# SH2_-_24V_BUCK-BOOST_CONVERTER.net
KiCad netlist of a schematic drawn in Altium Designer
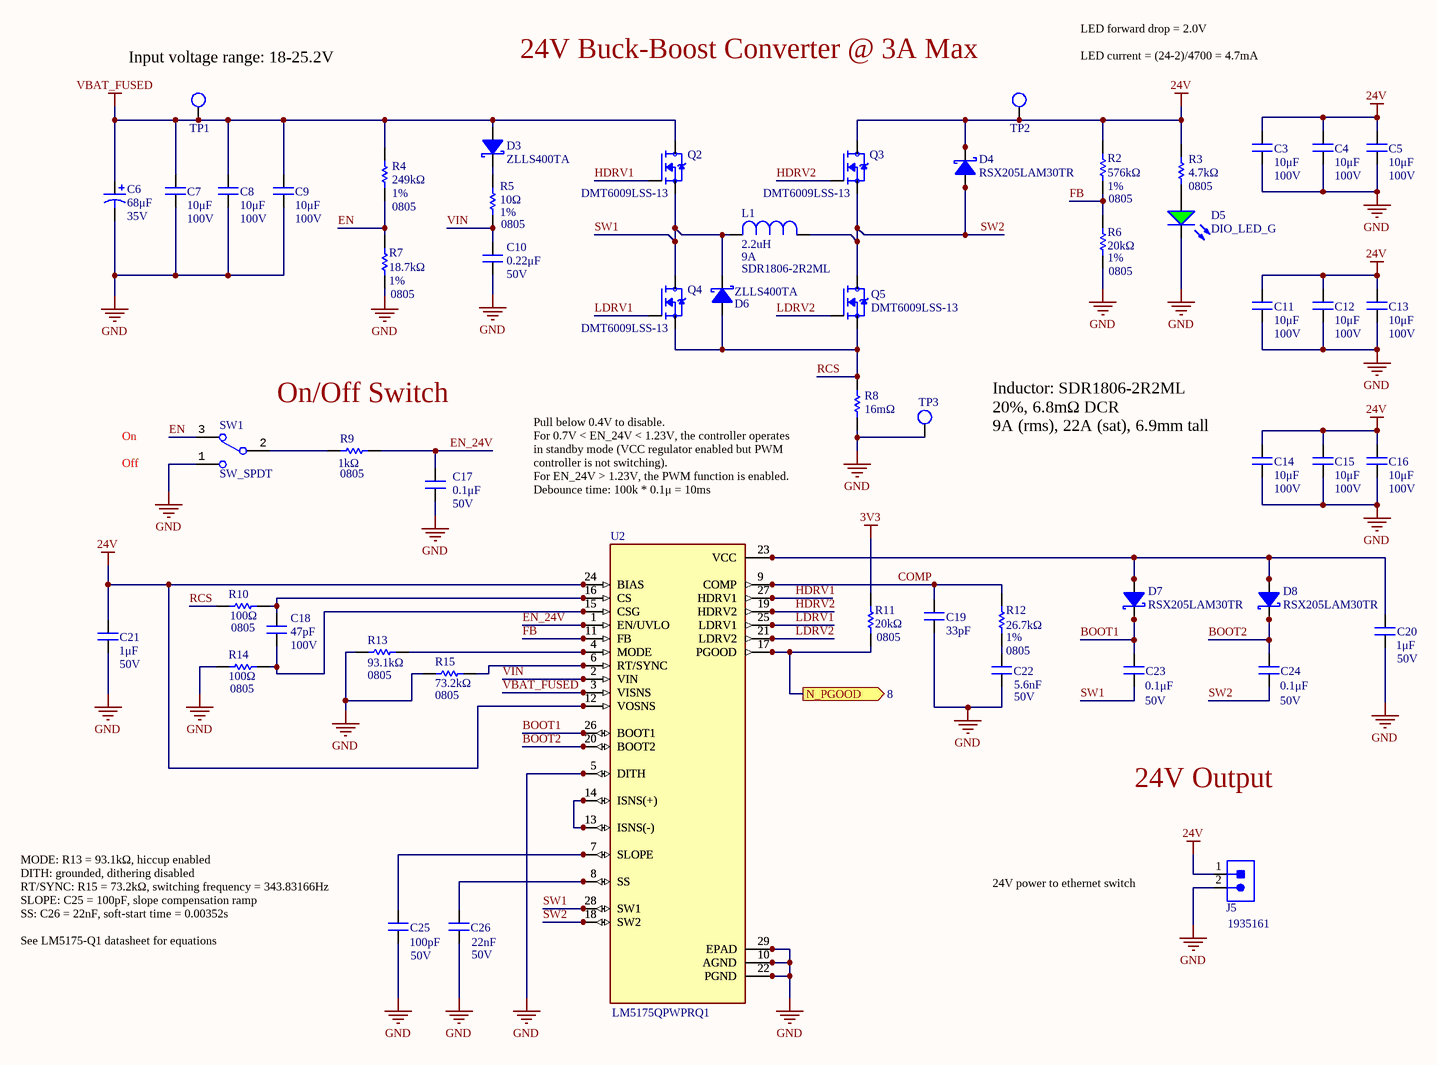
[diagram p0: SH2 - 24V BUCK-BOOST CONVERTER.SchDoc]

(export (version "E")
  (design (tool "Eeschema 10.0.6"))
  (components
    (comp (ref "C3")
      (value "10μF")
      (footprint "CAP1210")
      (description "CAP CER 10uF 100V X7S 10% 1210")
      (fields
        (field (name "TOLERANCE") "10%")
        (field (name "VOLTAGE RATING") "100V")
        (field (name "Comment") "CAP_10uF_100V_1210")
      )
      (libsource (lib "UWRT_Schematic_Library_2020") (part "CAP_10uF_100V_1210"))
    )
    (comp (ref "C4")
      (value "10μF")
      (footprint "CAP1210")
      (description "CAP CER 10uF 100V X7S 10% 1210")
      (fields
        (field (name "TOLERANCE") "10%")
        (field (name "VOLTAGE RATING") "100V")
        (field (name "Comment") "CAP_10uF_100V_1210")
      )
      (libsource (lib "UWRT_Schematic_Library_2020") (part "CAP_10uF_100V_1210"))
    )
    (comp (ref "C5")
      (value "10μF")
      (footprint "CAP1210")
      (description "CAP CER 10uF 100V X7S 10% 1210")
      (fields
        (field (name "TOLERANCE") "10%")
        (field (name "VOLTAGE RATING") "100V")
        (field (name "Comment") "CAP_10uF_100V_1210")
      )
      (libsource (lib "UWRT_Schematic_Library_2020") (part "CAP_10uF_100V_1210"))
    )
    (comp (ref "C6")
      (value "68μF")
      (footprint "RADIAL_NICHION_1V")
      (description "CAP ALUM 68UF 20% 35V SMD")
      (fields
        (field (name "TOLERANCE") "20%")
        (field (name "VOLTAGE RATING") "35V")
        (field (name "Comment") "CAP_68uF_35V_ALUM")
      )
      (libsource (lib "UWRT_Schematic_Library_2020") (part "CAP_68uF_35V_ALUM"))
    )
    (comp (ref "C7")
      (value "10μF")
      (footprint "CAP1210")
      (description "CAP CER 10uF 100V X7S 10% 1210")
      (fields
        (field (name "TOLERANCE") "10%")
        (field (name "VOLTAGE RATING") "100V")
        (field (name "Comment") "CAP_10uF_100V_1210")
      )
      (libsource (lib "UWRT_Schematic_Library_2020") (part "CAP_10uF_100V_1210"))
    )
    (comp (ref "C8")
      (value "10μF")
      (footprint "CAP1210")
      (description "CAP CER 10uF 100V X7S 10% 1210")
      (fields
        (field (name "TOLERANCE") "10%")
        (field (name "VOLTAGE RATING") "100V")
        (field (name "Comment") "CAP_10uF_100V_1210")
      )
      (libsource (lib "UWRT_Schematic_Library_2020") (part "CAP_10uF_100V_1210"))
    )
    (comp (ref "C9")
      (value "10μF")
      (footprint "CAP1210")
      (description "CAP CER 10uF 100V X7S 10% 1210")
      (fields
        (field (name "TOLERANCE") "10%")
        (field (name "VOLTAGE RATING") "100V")
        (field (name "Comment") "CAP_10uF_100V_1210")
      )
      (libsource (lib "UWRT_Schematic_Library_2020") (part "CAP_10uF_100V_1210"))
    )
    (comp (ref "C10")
      (value "0.22μF")
      (footprint "CAP2012")
      (description "CAP CER 0.22UF 50V X7R 0805")
      (fields
        (field (name "VOLTAGE RATING") "50V")
        (field (name "LCSC PART #") "C5378")
        (field (name "Comment") "CAP_0.22uF_50V_0805")
      )
      (libsource (lib "UWRT_Schematic_Library_2020") (part "CAP_0.22uF_50V_0805"))
    )
    (comp (ref "C11")
      (value "10μF")
      (footprint "CAP1210")
      (description "CAP CER 10uF 100V X7S 10% 1210")
      (fields
        (field (name "TOLERANCE") "10%")
        (field (name "VOLTAGE RATING") "100V")
        (field (name "Comment") "CAP_10uF_100V_1210")
      )
      (libsource (lib "UWRT_Schematic_Library_2020") (part "CAP_10uF_100V_1210"))
    )
    (comp (ref "C12")
      (value "10μF")
      (footprint "CAP1210")
      (description "CAP CER 10uF 100V X7S 10% 1210")
      (fields
        (field (name "TOLERANCE") "10%")
        (field (name "VOLTAGE RATING") "100V")
        (field (name "Comment") "CAP_10uF_100V_1210")
      )
      (libsource (lib "UWRT_Schematic_Library_2020") (part "CAP_10uF_100V_1210"))
    )
    (comp (ref "C13")
      (value "10μF")
      (footprint "CAP1210")
      (description "CAP CER 10uF 100V X7S 10% 1210")
      (fields
        (field (name "TOLERANCE") "10%")
        (field (name "VOLTAGE RATING") "100V")
        (field (name "Comment") "CAP_10uF_100V_1210")
      )
      (libsource (lib "UWRT_Schematic_Library_2020") (part "CAP_10uF_100V_1210"))
    )
    (comp (ref "C14")
      (value "10μF")
      (footprint "CAP1210")
      (description "CAP CER 10uF 100V X7S 10% 1210")
      (fields
        (field (name "TOLERANCE") "10%")
        (field (name "VOLTAGE RATING") "100V")
        (field (name "Comment") "CAP_10uF_100V_1210")
      )
      (libsource (lib "UWRT_Schematic_Library_2020") (part "CAP_10uF_100V_1210"))
    )
    (comp (ref "C15")
      (value "10μF")
      (footprint "CAP1210")
      (description "CAP CER 10uF 100V X7S 10% 1210")
      (fields
        (field (name "TOLERANCE") "10%")
        (field (name "VOLTAGE RATING") "100V")
        (field (name "Comment") "CAP_10uF_100V_1210")
      )
      (libsource (lib "UWRT_Schematic_Library_2020") (part "CAP_10uF_100V_1210"))
    )
    (comp (ref "C16")
      (value "10μF")
      (footprint "CAP1210")
      (description "CAP CER 10uF 100V X7S 10% 1210")
      (fields
        (field (name "TOLERANCE") "10%")
        (field (name "VOLTAGE RATING") "100V")
        (field (name "Comment") "CAP_10uF_100V_1210")
      )
      (libsource (lib "UWRT_Schematic_Library_2020") (part "CAP_10uF_100V_1210"))
    )
    (comp (ref "C17")
      (value "0.1μF")
      (footprint "CAP2012")
      (description "CAP CER 0.1UF 50V X7R 0805")
      (fields
        (field (name "VOLTAGE RATING") "50V")
        (field (name "TOLERANCE") "10%")
        (field (name "LCSC PART #") "C49678")
      )
      (libsource (lib "UWRT_Schematic_Library_2020") (part "CAP_0.1uF_50V_0805"))
    )
    (comp (ref "C18")
      (value "CAP_47pF_100V_0805")
      (footprint "CAP2012")
      (description "CAP CER 47PF 100V NPO 0805")
      (fields (field (name "VOLTAGE RATING") "100V") (field (name "CAPACITANCE") "47pF"))
      (libsource (lib "UWRT_Schematic_Library_2020") (part "CAP_47pF_100V_0805"))
    )
    (comp (ref "C19")
      (value "33pF")
      (footprint "CAP2012")
      (description "CAP CER 33PF 50V C0G/NP0 0805")
      (fields (field (name "Comment") "CAP_33pF_50V_0805"))
      (libsource (lib "UWRT_Schematic_Library_2020") (part "CAP_33pF_50V_0805"))
    )
    (comp (ref "C20")
      (value "1μF")
      (footprint "CAP2012")
      (description "CAP CER 1UF 50V X7R 0805")
      (fields
        (field (name "VOLTAGE RATING") "50V")
        (field (name "LCSC PART #") "C28323")
        (field (name "Comment") "CAP_1uF_50V_0805")
      )
      (libsource (lib "UWRT_Schematic_Library_2020") (part "CAP_1uF_50V_0805"))
    )
    (comp (ref "C21")
      (value "1μF")
      (footprint "CAP2012")
      (description "CAP CER 1UF 50V X7R 0805")
      (fields
        (field (name "VOLTAGE RATING") "50V")
        (field (name "LCSC PART #") "C28323")
        (field (name "Comment") "CAP_1uF_50V_0805")
      )
      (libsource (lib "UWRT_Schematic_Library_2020") (part "CAP_1uF_50V_0805"))
    )
    (comp (ref "C22")
      (value "CAP_5600pF_50V_0805")
      (footprint "CAP2012")
      (description "CAP CER 5600PF 50V C0G 0805")
      (fields
        (field (name "TOLERANCE") "5%")
        (field (name "CAPACITANCE") "5.6nF")
        (field (name "VOLTAGE RATING") "50V")
      )
      (libsource (lib "UWRT_Schematic_Library_2020") (part "CAP_5600pF_50V_0805"))
    )
    (comp (ref "C23")
      (value "0.1μF")
      (footprint "CAP2012")
      (description "CAP CER 0.1UF 50V X7R 0805")
      (fields
        (field (name "TOLERANCE") "10%")
        (field (name "VOLTAGE RATING") "50V")
        (field (name "LCSC PART #") "C49678")
      )
      (libsource (lib "UWRT_Schematic_Library_2020") (part "CAP_0.1uF_50V_0805"))
    )
    (comp (ref "C24")
      (value "0.1μF")
      (footprint "CAP2012")
      (description "CAP CER 0.1UF 50V X7R 0805")
      (fields
        (field (name "TOLERANCE") "10%")
        (field (name "VOLTAGE RATING") "50V")
        (field (name "LCSC PART #") "C49678")
      )
      (libsource (lib "UWRT_Schematic_Library_2020") (part "CAP_0.1uF_50V_0805"))
    )
    (comp (ref "C25")
      (value "100pF")
      (footprint "CAP2012")
      (description "CAP CER 100PF 50V C0G/NP0 0805")
      (fields (field (name "VOLTAGE RATING") "50V") (field (name "Comment") "CAP_100pF_50V_0805"))
      (libsource (lib "UWRT_Schematic_Library_2020") (part "CAP_100pF_50V_0805"))
    )
    (comp (ref "C26")
      (value "22nF")
      (footprint "CAP2012")
      (description "CAP CER 0.022UF 50V C0G 0805")
      (fields
        (field (name "VOLTAGE RATING") "50V")
        (field (name "LCSC PART #") "C1729")
        (field (name "Comment") "CAP_0.022uF_50V_0805")
      )
      (libsource (lib "UWRT_Schematic_Library_2020") (part "CAP_0.022uF_50V_0805"))
    )
    (comp (ref "D3")
      (value "DIO_SCHOTTKY_40V_520mA")
      (footprint "SOD-323")
      (description "DIODE SCHOTTKY 40V 520MA SOD323")
      (fields (field (name "MANUFACTURER PART NUMBER 1") "ZLLS400TA"))
      (libsource (lib "UWRT_Schematic_Library_2020") (part "DIO_SCHOTTKY_40V_520mA"))
    )
    (comp (ref "D4")
      (value "DIO_SCHOTTKY_30V_2A")
      (footprint "SOD-128")
      (description "DIODE SCHOTTKY 30V 2A PMDTM")
      (fields (field (name "MANUFACTURER PART NUMBER 1") "RSX205LAM30TR"))
      (libsource (lib "UWRT_Schematic_Library_2020") (part "DIO_SCHOTTKY_30V_2A"))
    )
    (comp (ref "D5")
      (value "DIO_LED_G")
      (footprint "LED_0805_GREEN")
      (description "LED GREEN DIFFUSED 0805 SMD")
      (libsource (lib "UWRT_Schematic_Library_2020") (part "DIO_LED_G"))
    )
    (comp (ref "D6")
      (value "DIO_SCHOTTKY_40V_520mA")
      (footprint "SOD-323")
      (description "DIODE SCHOTTKY 40V 520MA SOD323")
      (fields (field (name "MANUFACTURER PART NUMBER 1") "ZLLS400TA"))
      (libsource (lib "UWRT_Schematic_Library_2020") (part "DIO_SCHOTTKY_40V_520mA"))
    )
    (comp (ref "D7")
      (value "DIO_SCHOTTKY_30V_2A")
      (footprint "SOD-128")
      (description "DIODE SCHOTTKY 30V 2A PMDTM")
      (fields (field (name "MANUFACTURER PART NUMBER 1") "RSX205LAM30TR"))
      (libsource (lib "UWRT_Schematic_Library_2020") (part "DIO_SCHOTTKY_30V_2A"))
    )
    (comp (ref "D8")
      (value "DIO_SCHOTTKY_30V_2A")
      (footprint "SOD-128")
      (description "DIODE SCHOTTKY 30V 2A PMDTM")
      (fields (field (name "MANUFACTURER PART NUMBER 1") "RSX205LAM30TR"))
      (libsource (lib "UWRT_Schematic_Library_2020") (part "DIO_SCHOTTKY_30V_2A"))
    )
    (comp (ref "J5")
      (value "CON_2M_TERM")
      (footprint "1935161")
      (description "TERM BLK 2POS SIDE ENTRY 5MM")
      (fields (field (name "VOLTAGE") "300V") (field (name "MANUFACTURER PART NUMBER 1") "1935161"))
      (libsource (lib "UWRT_Schematic_Library_2020") (part "CON_2M_TERM"))
    )
    (comp (ref "L1")
      (value "IND_2.2uH_9A")
      (footprint "IND_BOURNS_SDR1806")
      (description "FIXED IND 2.2UH 9A 6.8 MOHM SMD")
      (fields
        (field (name "TOLERANCE") "20%")
        (field (name "CURRENT RATING") "9A")
        (field (name "MANUFACTURER PART NUMBER 1") "SDR1806-2R2ML")
        (field (name "INDUCTANCE") "2.2uH")
      )
      (libsource (lib "UWRT_Schematic_Library_2020") (part "IND_2.2uH_9A"))
    )
    (comp (ref "Q2")
      (value "NMOS_60V_10.8A")
      (footprint "TRANS_DMP2002UPS-13")
      (description "MOSFET BVDSS: 41V 60V,SO-8,T&R,2")
      (fields
        (field (name "MANUFACTURER PART NUMBER 1") "DMT6009LSS-13")
        (field (name "LCSC PART #") "C508211")
      )
      (libsource (lib "UWRT_Schematic_Library_2020") (part "NMOS_60V_10.8A"))
    )
    (comp (ref "Q3")
      (value "NMOS_60V_10.8A")
      (footprint "TRANS_DMP2002UPS-13")
      (description "MOSFET BVDSS: 41V 60V,SO-8,T&R,2")
      (fields
        (field (name "MANUFACTURER PART NUMBER 1") "DMT6009LSS-13")
        (field (name "LCSC PART #") "C508211")
      )
      (libsource (lib "UWRT_Schematic_Library_2020") (part "NMOS_60V_10.8A"))
    )
    (comp (ref "Q4")
      (value "NMOS_60V_10.8A")
      (footprint "TRANS_DMP2002UPS-13")
      (description "MOSFET BVDSS: 41V 60V,SO-8,T&R,2")
      (fields
        (field (name "MANUFACTURER PART NUMBER 1") "DMT6009LSS-13")
        (field (name "LCSC PART #") "C508211")
      )
      (libsource (lib "UWRT_Schematic_Library_2020") (part "NMOS_60V_10.8A"))
    )
    (comp (ref "Q5")
      (value "NMOS_60V_10.8A")
      (footprint "TRANS_DMP2002UPS-13")
      (description "MOSFET BVDSS: 41V 60V,SO-8,T&R,2")
      (fields
        (field (name "MANUFACTURER PART NUMBER 1") "DMT6009LSS-13")
        (field (name "LCSC PART #") "C508211")
      )
      (libsource (lib "UWRT_Schematic_Library_2020") (part "NMOS_60V_10.8A"))
    )
    (comp (ref "R2")
      (value "576kΩ")
      (footprint "RESC0805")
      (description "RES 576K OHM 1% 1/8W 0805")
      (fields
        (field (name "TOLERANCE") "1%")
        (field (name "LCSC PART #") "C17760")
        (field (name "PACKAGE/FOOTPRINT") "0805")
        (field (name "Comment") "RES_576kΩ_0805_1%")
      )
      (libsource (lib "UWRT_Schematic_Library_2020") (part "RES_576kΩ_0805_1%"))
    )
    (comp (ref "R3")
      (value "4.7kΩ")
      (footprint "RESC0805")
      (description "RES 4.7K OHM 5% 1/8W 0805")
      (fields
        (field (name "LCSC PART #") "C17673")
        (field (name "PACKAGE/FOOTPRINT") "0805")
        (field (name "Comment") "RES_4.7kΩ_0805_5%")
      )
      (libsource (lib "UWRT_Schematic_Library_2020") (part "RES_4.7kΩ_0805_5%"))
    )
    (comp (ref "R4")
      (value "249kΩ")
      (footprint "RESC0805")
      (description "RES 249K OHM 1% 1/8W 0805")
      (fields
        (field (name "TOLERANCE") "1%")
        (field (name "LCSC PART #") "C25825")
        (field (name "PACKAGE/FOOTPRINT") "0805")
        (field (name "Comment") "RES_249kΩ_0805_1%")
      )
      (libsource (lib "UWRT_Schematic_Library_2020") (part "RES_249kΩ_0805_1%"))
    )
    (comp (ref "R5")
      (value "10Ω")
      (footprint "RESC0805")
      (description "RES 10 OHM 1% 1/8W 0805")
      (fields
        (field (name "TOLERANCE") "1%")
        (field (name "LCSC PART #") "C17415")
        (field (name "PACKAGE/FOOTPRINT") "0805")
        (field (name "Comment") "RES_10Ω_0805_1%")
      )
      (libsource (lib "UWRT_Schematic_Library_2020") (part "RES_10Ω_0805_1%"))
    )
    (comp (ref "R6")
      (value "20kΩ")
      (footprint "RESC0805")
      (description "RES 20K OHM 1% 1/8W 0805")
      (fields
        (field (name "TOLERANCE") "1%")
        (field (name "LCSC PART #") "C4328")
        (field (name "PACKAGE/FOOTPRINT") "0805")
        (field (name "Comment") "RES_20kΩ_0805_1%")
      )
      (libsource (lib "UWRT_Schematic_Library_2020") (part "RES_20kΩ_0805_1%"))
    )
    (comp (ref "R7")
      (value "18.7kΩ")
      (footprint "RESC0805")
      (description "RES 18.7K OHM 1% 1/8W 0805")
      (fields
        (field (name "TOLERANCE") "1%")
        (field (name "LCSC PART #") "C17499")
        (field (name "PACKAGE/FOOTPRINT") "0805")
        (field (name "Comment") "RES_18.7kΩ_0805_1%")
      )
      (libsource (lib "UWRT_Schematic_Library_2020") (part "RES_18.7kΩ_0805_1%"))
    )
    (comp (ref "R8")
      (value "16mΩ")
      (footprint "RESC1632X60N")
      (description "RES 0.016 OHM 1W 1206 WIDE")
      (fields (field (name "TOLERANCE") "1%") (field (name "Comment") "RES_16mΩ_1206_1%"))
      (libsource (lib "UWRT_Schematic_Library_2020") (part "RES_16mΩ_1206_1%"))
    )
    (comp (ref "R9")
      (value "RES_1kΩ_0805_1%")
      (footprint "RESC0805")
      (description "RES 1K OHM 1% 1/8W 0805")
      (fields
        (field (name "TOLERANCE") "1%")
        (field (name "RESISTANCE") "1kΩ")
        (field (name "LCSC PART #") "C17513")
        (field (name "PACKAGE/FOOTPRINT") "0805")
      )
      (libsource (lib "UWRT_Schematic_Library_2020") (part "RES_1kΩ_0805_1%"))
    )
    (comp (ref "R10")
      (value "100Ω")
      (footprint "RESC0805")
      (description "RES 100 OHM 1% 1/8W 0805")
      (fields
        (field (name "LCSC PART #") "C1790")
        (field (name "PACKAGE/FOOTPRINT") "0805")
        (field (name "Comment") "RES_100Ω_0805_1%")
      )
      (libsource (lib "UWRT_Schematic_Library_2020") (part "RES_100Ω_0805_1%"))
    )
    (comp (ref "R11")
      (value "20kΩ")
      (footprint "RESC0805")
      (description "RES 20K OHM 1% 1/8W 0805")
      (fields
        (field (name "TOLERANCE") "1%")
        (field (name "LCSC PART #") "C4328")
        (field (name "PACKAGE/FOOTPRINT") "0805")
      )
      (libsource (lib "UWRT_Schematic_Library_2020") (part "RES_20kΩ_0805_1%"))
    )
    (comp (ref "R12")
      (value "26.7kΩ")
      (footprint "RESC0805")
      (description "RES 26.7K OHM 1% 1/8W 0805")
      (fields
        (field (name "TOLERANCE") "1%")
        (field (name "LCSC PART #") "C17581")
        (field (name "PACKAGE/FOOTPRINT") "0805")
        (field (name "Comment") "RES_26.7kΩ_0805_1%")
      )
      (libsource (lib "UWRT_Schematic_Library_2020") (part "RES_26.7kΩ_0805_1%"))
    )
    (comp (ref "R13")
      (value "93.1kΩ")
      (footprint "RESC0805")
      (description "RES 93.1K OHM 1% 1/8W 0805")
      (fields
        (field (name "TOLERANCE") "1%")
        (field (name "LCSC PART #") "C17869")
        (field (name "PACKAGE/FOOTPRINT") "0805")
      )
      (libsource (lib "UWRT_Schematic_Library_2020") (part "RES_93.1kΩ_0805_1%"))
    )
    (comp (ref "R14")
      (value "100Ω")
      (footprint "RESC0805")
      (description "RES 100 OHM 1% 1/8W 0805")
      (fields
        (field (name "LCSC PART #") "C1790")
        (field (name "PACKAGE/FOOTPRINT") "0805")
        (field (name "Comment") "RES_100Ω_0805_1%")
      )
      (libsource (lib "UWRT_Schematic_Library_2020") (part "RES_100Ω_0805_1%"))
    )
    (comp (ref "R15")
      (value "73.2kΩ")
      (footprint "RESC0805")
      (description "RES 73.2K OHM 1% 1/8W 0805")
      (fields
        (field (name "TOLERANCE") "1%")
        (field (name "LCSC PART #") "C17814")
        (field (name "PACKAGE/FOOTPRINT") "0805")
      )
      (libsource (lib "UWRT_Schematic_Library_2020") (part "RES_73.2kΩ_0805_1%"))
    )
    (comp (ref "SW1")
      (value "SW_SPDT")
      (footprint "100SP1T1B4M2QE")
      (description "SWITCH TOGGLE SPDT 5A 120V")
      (libsource (lib "UWRT_Schematic_Library_2020") (part "SW_SPDT"))
    )
    (comp (ref "TP1")
      (value "TESTPOINT_LOOP")
      (footprint "TESTPOINT_LOOP")
      (description "PC TEST POINT MINIATURE WHITE")
      (libsource (lib "UWRT_Schematic_Library_2020") (part "TESTPOINT_LOOP"))
    )
    (comp (ref "TP2")
      (value "TESTPOINT_LOOP")
      (footprint "TESTPOINT_LOOP")
      (description "PC TEST POINT MINIATURE WHITE")
      (libsource (lib "UWRT_Schematic_Library_2020") (part "TESTPOINT_LOOP"))
    )
    (comp (ref "TP3")
      (value "TESTPOINT_LOOP")
      (footprint "TESTPOINT_LOOP")
      (description "PC TEST POINT MINIATURE WHITE")
      (libsource (lib "UWRT_Schematic_Library_2020") (part "TESTPOINT_LOOP"))
    )
    (comp (ref "U2")
      (value "LM5175PWPR")
      (footprint "IC_TPS61196PWPRQ1")
      (description "IC REG CTRLR BUCK-BOOST 28HTSSOP")
      (fields
        (field (name "MANUFACTURER PART NUMBER 1") "LM5175QPWPRQ1")
        (field (name "LCSC PART #") "C113356")
      )
      (libsource (lib "UWRT_Schematic_Library_2020") (part "LM5175PWPR"))
    )
  )
  (nets
    (net (code "1") (name "/BOOT1") (class "Default")
      (node (ref "C23") (pin "2") (pinfunction "2_2") (pintype "passive"))
      (node (ref "D7") (pin "2") (pinfunction "Cathode_2") (pintype "passive"))
      (node (ref "U2") (pin "26") (pinfunction "BOOT1_26") (pintype "bidirectional"))
    )
    (net (code "2") (name "/BOOT2") (class "Default")
      (node (ref "C24") (pin "2") (pinfunction "2_2") (pintype "passive"))
      (node (ref "D8") (pin "2") (pinfunction "Cathode_2") (pintype "passive"))
      (node (ref "U2") (pin "20") (pinfunction "BOOT2_20") (pintype "bidirectional"))
    )
    (net (code "3") (name "/COMP") (class "Default")
      (node (ref "C19") (pin "2") (pinfunction "2_2") (pintype "passive"))
      (node (ref "R12") (pin "2") (pinfunction "2_2") (pintype "passive"))
      (node (ref "U2") (pin "9") (pinfunction "COMP_9") (pintype "output"))
    )
    (net (code "4") (name "/EN") (class "Default")
      (node (ref "R4") (pin "1") (pinfunction "1_1") (pintype "passive"))
      (node (ref "R7") (pin "2") (pinfunction "2_2") (pintype "passive"))
      (node (ref "SW1") (pin "3") (pinfunction "3_3") (pintype "passive"))
    )
    (net (code "5") (name "/EN_24V") (class "Default")
      (node (ref "C17") (pin "2") (pinfunction "2_2") (pintype "passive"))
      (node (ref "R9") (pin "2") (pinfunction "2_2") (pintype "passive"))
      (node (ref "U2") (pin "1") (pinfunction "EN/UVLO_1") (pintype "input"))
    )
    (net (code "6") (name "/FB") (class "Default")
      (node (ref "R2") (pin "1") (pinfunction "1_1") (pintype "passive"))
      (node (ref "R6") (pin "2") (pinfunction "2_2") (pintype "passive"))
      (node (ref "U2") (pin "11") (pinfunction "FB_11") (pintype "input"))
    )
    (net (code "7") (name "/HDRV1") (class "Default")
      (node (ref "Q2") (pin "3") (pinfunction "G_3") (pintype "passive"))
      (node (ref "U2") (pin "27") (pinfunction "HDRV1_27") (pintype "output"))
    )
    (net (code "8") (name "/HDRV2") (class "Default")
      (node (ref "Q3") (pin "3") (pinfunction "G_3") (pintype "passive"))
      (node (ref "U2") (pin "19") (pinfunction "HDRV2_19") (pintype "output"))
    )
    (net (code "9") (name "/LDRV1") (class "Default")
      (node (ref "Q4") (pin "3") (pinfunction "G_3") (pintype "passive"))
      (node (ref "U2") (pin "25") (pinfunction "LDRV1_25") (pintype "output"))
    )
    (net (code "10") (name "/LDRV2") (class "Default")
      (node (ref "Q5") (pin "3") (pinfunction "G_3") (pintype "passive"))
      (node (ref "U2") (pin "21") (pinfunction "LDRV2_21") (pintype "output"))
    )
    (net (code "11") (name "/N_PGOOD") (class "Default")
      (node (ref "R11") (pin "1") (pinfunction "1_1") (pintype "passive"))
      (node (ref "U2") (pin "17") (pinfunction "PGOOD_17") (pintype "output"))
    )
    (net (code "12") (name "/RCS") (class "Default")
      (node (ref "D6") (pin "1") (pinfunction "Anode_1") (pintype "passive"))
      (node (ref "Q4") (pin "2") (pinfunction "S_2") (pintype "passive"))
      (node (ref "Q5") (pin "2") (pinfunction "S_2") (pintype "passive"))
      (node (ref "R10") (pin "1") (pinfunction "1_1") (pintype "passive"))
      (node (ref "R8") (pin "2") (pinfunction "2_2") (pintype "passive"))
    )
    (net (code "13") (name "/SW1") (class "Default")
      (node (ref "C23") (pin "1") (pinfunction "1_1") (pintype "passive"))
      (node (ref "D6") (pin "2") (pinfunction "Cathode_2") (pintype "passive"))
      (node (ref "L1") (pin "2") (pinfunction "2_2") (pintype "passive"))
      (node (ref "Q2") (pin "2") (pinfunction "S_2") (pintype "passive"))
      (node (ref "Q4") (pin "1") (pinfunction "D_1") (pintype "passive"))
      (node (ref "U2") (pin "28") (pinfunction "SW1_28") (pintype "bidirectional"))
    )
    (net (code "14") (name "/SW2") (class "Default")
      (node (ref "C24") (pin "1") (pinfunction "1_1") (pintype "passive"))
      (node (ref "D4") (pin "1") (pinfunction "Anode_1") (pintype "passive"))
      (node (ref "L1") (pin "1") (pinfunction "1_1") (pintype "passive"))
      (node (ref "Q3") (pin "2") (pinfunction "S_2") (pintype "passive"))
      (node (ref "Q5") (pin "1") (pinfunction "D_1") (pintype "passive"))
      (node (ref "U2") (pin "18") (pinfunction "SW2_18") (pintype "bidirectional"))
    )
    (net (code "15") (name "/VIN") (class "Default")
      (node (ref "C10") (pin "2") (pinfunction "2_2") (pintype "passive"))
      (node (ref "R5") (pin "1") (pinfunction "1_1") (pintype "passive"))
      (node (ref "U2") (pin "2") (pinfunction "VIN_2") (pintype "input"))
    )
    (net (code "16") (name "3V3") (class "Default")
      (node (ref "R11") (pin "2") (pinfunction "2_2") (pintype "passive"))
    )
    (net (code "17") (name "24V") (class "Default")
      (node (ref "C11") (pin "1") (pinfunction "1_1") (pintype "passive"))
      (node (ref "C12") (pin "1") (pinfunction "1_1") (pintype "passive"))
      (node (ref "C13") (pin "2") (pinfunction "2_2") (pintype "passive"))
      (node (ref "C14") (pin "1") (pinfunction "1_1") (pintype "passive"))
      (node (ref "C15") (pin "1") (pinfunction "1_1") (pintype "passive"))
      (node (ref "C16") (pin "2") (pinfunction "2_2") (pintype "passive"))
      (node (ref "C21") (pin "2") (pinfunction "2_2") (pintype "passive"))
      (node (ref "C3") (pin "1") (pinfunction "1_1") (pintype "passive"))
      (node (ref "C4") (pin "1") (pinfunction "1_1") (pintype "passive"))
      (node (ref "C5") (pin "2") (pinfunction "2_2") (pintype "passive"))
      (node (ref "D4") (pin "2") (pinfunction "Cathode_2") (pintype "passive"))
      (node (ref "J5") (pin "1") (pinfunction "1_1") (pintype "passive"))
      (node (ref "Q3") (pin "1") (pinfunction "D_1") (pintype "passive"))
      (node (ref "R2") (pin "2") (pinfunction "2_2") (pintype "passive"))
      (node (ref "R3") (pin "2") (pinfunction "2_2") (pintype "passive"))
      (node (ref "TP2") (pin "1") (pintype "passive"))
      (node (ref "U2") (pin "12") (pinfunction "VOSNS_12") (pintype "input"))
      (node (ref "U2") (pin "24") (pinfunction "BIAS_24") (pintype "input"))
    )
    (net (code "18") (name "GND") (class "Default")
      (node (ref "C10") (pin "1") (pinfunction "1_1") (pintype "passive"))
      (node (ref "C11") (pin "2") (pinfunction "2_2") (pintype "passive"))
      (node (ref "C12") (pin "2") (pinfunction "2_2") (pintype "passive"))
      (node (ref "C13") (pin "1") (pinfunction "1_1") (pintype "passive"))
      (node (ref "C14") (pin "2") (pinfunction "2_2") (pintype "passive"))
      (node (ref "C15") (pin "2") (pinfunction "2_2") (pintype "passive"))
      (node (ref "C16") (pin "1") (pinfunction "1_1") (pintype "passive"))
      (node (ref "C17") (pin "1") (pinfunction "1_1") (pintype "passive"))
      (node (ref "C19") (pin "1") (pinfunction "1_1") (pintype "passive"))
      (node (ref "C20") (pin "1") (pinfunction "1_1") (pintype "passive"))
      (node (ref "C21") (pin "1") (pinfunction "1_1") (pintype "passive"))
      (node (ref "C22") (pin "1") (pinfunction "1_1") (pintype "passive"))
      (node (ref "C25") (pin "1") (pinfunction "1_1") (pintype "passive"))
      (node (ref "C26") (pin "1") (pinfunction "1_1") (pintype "passive"))
      (node (ref "C3") (pin "2") (pinfunction "2_2") (pintype "passive"))
      (node (ref "C4") (pin "2") (pinfunction "2_2") (pintype "passive"))
      (node (ref "C5") (pin "1") (pinfunction "1_1") (pintype "passive"))
      (node (ref "C6") (pin "2") (pinfunction "2_2") (pintype "passive"))
      (node (ref "C7") (pin "1") (pinfunction "1_1") (pintype "passive"))
      (node (ref "C8") (pin "1") (pinfunction "1_1") (pintype "passive"))
      (node (ref "C9") (pin "1") (pinfunction "1_1") (pintype "passive"))
      (node (ref "D5") (pin "2") (pinfunction "K_2") (pintype "passive"))
      (node (ref "J5") (pin "2") (pinfunction "2_2") (pintype "passive"))
      (node (ref "R13") (pin "1") (pinfunction "1_1") (pintype "passive"))
      (node (ref "R14") (pin "1") (pinfunction "1_1") (pintype "passive"))
      (node (ref "R15") (pin "1") (pinfunction "1_1") (pintype "passive"))
      (node (ref "R6") (pin "1") (pinfunction "1_1") (pintype "passive"))
      (node (ref "R7") (pin "1") (pinfunction "1_1") (pintype "passive"))
      (node (ref "R8") (pin "1") (pinfunction "1_1") (pintype "passive"))
      (node (ref "SW1") (pin "1") (pinfunction "1_1") (pintype "passive"))
      (node (ref "TP3") (pin "1") (pintype "passive"))
      (node (ref "U2") (pin "10") (pinfunction "AGND_10") (pintype "power_in"))
      (node (ref "U2") (pin "22") (pinfunction "PGND_22") (pintype "power_in"))
      (node (ref "U2") (pin "29") (pinfunction "EPAD_29") (pintype "power_in"))
      (node (ref "U2") (pin "5") (pinfunction "DITH_5") (pintype "bidirectional"))
    )
    (net (code "19") (name "Net-(C22-Pad2)") (class "Default")
      (node (ref "C22") (pin "2") (pinfunction "2_2") (pintype "passive"))
      (node (ref "R12") (pin "1") (pinfunction "1_1") (pintype "passive"))
    )
    (net (code "20") (name "Net-(D3-Cathode)") (class "Default")
      (node (ref "D3") (pin "2") (pinfunction "Cathode_2") (pintype "passive"))
      (node (ref "R5") (pin "2") (pinfunction "2_2") (pintype "passive"))
    )
    (net (code "21") (name "Net-(D5-A)") (class "Default")
      (node (ref "D5") (pin "1") (pinfunction "A_1") (pintype "passive"))
      (node (ref "R3") (pin "1") (pinfunction "1_1") (pintype "passive"))
    )
    (net (code "22") (name "Net-(D7-Anode)") (class "Default")
      (node (ref "C20") (pin "2") (pinfunction "2_2") (pintype "passive"))
      (node (ref "D7") (pin "1") (pinfunction "Anode_1") (pintype "passive"))
      (node (ref "D8") (pin "1") (pinfunction "Anode_1") (pintype "passive"))
      (node (ref "U2") (pin "23") (pinfunction "VCC_23") (pintype "power_in"))
    )
    (net (code "23") (name "Net-(R9-Pad1)") (class "Default")
      (node (ref "R9") (pin "1") (pinfunction "1_1") (pintype "passive"))
      (node (ref "SW1") (pin "2") (pinfunction "2_2") (pintype "passive"))
    )
    (net (code "24") (name "Net-(U2-CS)") (class "Default")
      (node (ref "C18") (pin "1") (pinfunction "1_1") (pintype "passive"))
      (node (ref "R10") (pin "2") (pinfunction "2_2") (pintype "passive"))
      (node (ref "U2") (pin "16") (pinfunction "CS_16") (pintype "input"))
    )
    (net (code "25") (name "Net-(U2-CSG)") (class "Default")
      (node (ref "C18") (pin "2") (pinfunction "2_2") (pintype "passive"))
      (node (ref "R14") (pin "2") (pinfunction "2_2") (pintype "passive"))
      (node (ref "U2") (pin "15") (pinfunction "CSG_15") (pintype "input"))
    )
    (net (code "26") (name "Net-(U2-ISNS(+))") (class "Default")
      (node (ref "U2") (pin "13") (pinfunction "ISNS(-)_13") (pintype "bidirectional"))
      (node (ref "U2") (pin "14") (pinfunction "ISNS(+)_14") (pintype "bidirectional"))
    )
    (net (code "27") (name "Net-(U2-MODE)") (class "Default")
      (node (ref "R13") (pin "2") (pinfunction "2_2") (pintype "passive"))
      (node (ref "U2") (pin "4") (pinfunction "MODE_4") (pintype "input"))
    )
    (net (code "28") (name "Net-(U2-RT{slash}SYNC)") (class "Default")
      (node (ref "R15") (pin "2") (pinfunction "2_2") (pintype "passive"))
      (node (ref "U2") (pin "6") (pinfunction "RT/SYNC_6") (pintype "input"))
    )
    (net (code "29") (name "Net-(U2-SLOPE)") (class "Default")
      (node (ref "C25") (pin "2") (pinfunction "2_2") (pintype "passive"))
      (node (ref "U2") (pin "7") (pinfunction "SLOPE_7") (pintype "bidirectional"))
    )
    (net (code "30") (name "Net-(U2-SS)") (class "Default")
      (node (ref "C26") (pin "2") (pinfunction "2_2") (pintype "passive"))
      (node (ref "U2") (pin "8") (pinfunction "SS_8") (pintype "bidirectional"))
    )
    (net (code "31") (name "VBAT_FUSED") (class "Default")
      (node (ref "C6") (pin "1") (pinfunction "1_1") (pintype "passive"))
      (node (ref "C7") (pin "2") (pinfunction "2_2") (pintype "passive"))
      (node (ref "C8") (pin "2") (pinfunction "2_2") (pintype "passive"))
      (node (ref "C9") (pin "2") (pinfunction "2_2") (pintype "passive"))
      (node (ref "D3") (pin "1") (pinfunction "Anode_1") (pintype "passive"))
      (node (ref "Q2") (pin "1") (pinfunction "D_1") (pintype "passive"))
      (node (ref "R4") (pin "2") (pinfunction "2_2") (pintype "passive"))
      (node (ref "TP1") (pin "1") (pintype "passive"))
      (node (ref "U2") (pin "3") (pinfunction "VISNS_3") (pintype "input"))
    )
  )
)
